# MQTTGateWay.net
KiCad netlist of a schematic drawn in EAGLE
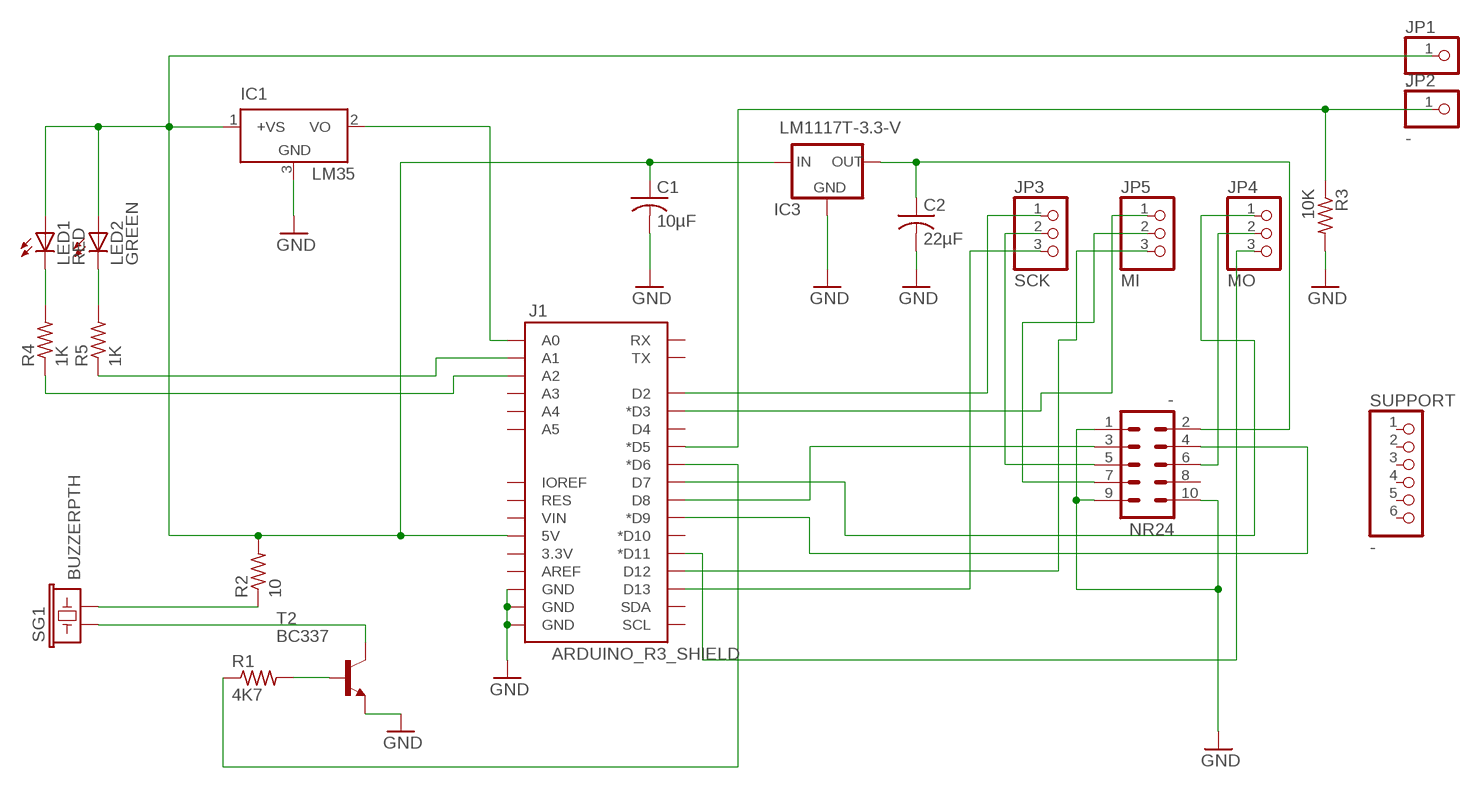
[diagram p0: schematic, sheet 1]

(export (version "E")
  (design (tool "Eeschema 10.0.6"))
  (components
    (comp (ref "C1")
      (value "10µF")
      (footprint "eagle-import:C025-024X044")
      (libsource (lib "eagle-import") (part "C-US025-024X044"))
    )
    (comp (ref "C2")
      (value "22µF")
      (footprint "eagle-import:C025-024X044")
      (libsource (lib "eagle-import") (part "C-US025-024X044"))
    )
    (comp (ref "IC1")
      (value "LM35")
      (footprint "eagle-import:TO92")
      (libsource (lib "eagle-import") (part "LM35CZ"))
    )
    (comp (ref "IC3")
      (value "LM1117T-3.3-V")
      (footprint "eagle-import:TO220V")
      (libsource (lib "eagle-import") (part "LM1117T--V3.3"))
    )
    (comp (ref "J1")
      (value "ARDUINO_R3_SHIELD")
      (footprint "eagle-import:UNO_R3_SHIELD")
      (libsource (lib "eagle-import") (part "ARDUINO_R3_SHIELD"))
    )
    (comp (ref "JP1")
      (value "-")
      (footprint "eagle-import:1X01")
      (libsource (lib "eagle-import") (part "PINHD-1X1"))
    )
    (comp (ref "JP2")
      (value "-")
      (footprint "eagle-import:1X01")
      (libsource (lib "eagle-import") (part "PINHD-1X1"))
    )
    (comp (ref "JP3")
      (value "SCK")
      (footprint "eagle-import:1X03")
      (libsource (lib "eagle-import") (part "PINHD-1X3"))
    )
    (comp (ref "JP4")
      (value "MO")
      (footprint "eagle-import:1X03")
      (libsource (lib "eagle-import") (part "PINHD-1X3"))
    )
    (comp (ref "JP5")
      (value "MI")
      (footprint "eagle-import:1X03")
      (libsource (lib "eagle-import") (part "PINHD-1X3"))
    )
    (comp (ref "LED1")
      (value "RED")
      (footprint "eagle-import:LED3MM")
      (libsource (lib "eagle-import") (part "LED3MM"))
    )
    (comp (ref "LED2")
      (value "GREEN")
      (footprint "eagle-import:LED3MM")
      (libsource (lib "eagle-import") (part "LED3MM"))
    )
    (comp (ref "NR24")
      (value "-")
      (footprint "eagle-import:MA05-2")
      (libsource (lib "eagle-import") (part "MA05-2"))
    )
    (comp (ref "R1")
      (value "4K7")
      (footprint "eagle-import:0207_10")
      (libsource (lib "eagle-import") (part "R-US_0207/10"))
    )
    (comp (ref "R2")
      (value "10")
      (footprint "eagle-import:0207_10")
      (libsource (lib "eagle-import") (part "R-US_0207/10"))
    )
    (comp (ref "R3")
      (value "10K")
      (footprint "eagle-import:0207_10")
      (libsource (lib "eagle-import") (part "R-US_0207/10"))
    )
    (comp (ref "R4")
      (value "1K")
      (footprint "eagle-import:0207_10")
      (libsource (lib "eagle-import") (part "R-US_0207/10"))
    )
    (comp (ref "R5")
      (value "1K")
      (footprint "eagle-import:0207_10")
      (libsource (lib "eagle-import") (part "R-US_0207/10"))
    )
    (comp (ref "SG1")
      (value "BUZZERPTH")
      (footprint "eagle-import:BUZZER-12MM")
      (libsource (lib "eagle-import") (part "BUZZERPTH"))
    )
    (comp (ref "SUPPORT")
      (value "-")
      (footprint "eagle-import:1X06")
      (libsource (lib "eagle-import") (part "PINHD-1X6"))
    )
    (comp (ref "T2")
      (value "BC337")
      (footprint "eagle-import:TO92")
      (libsource (lib "eagle-import") (part "BC337"))
    )
  )
  (nets
    (net (code "1") (name "GND") (class "Default")
      (node (ref "C1") (pin "2") (pinfunction "2_2") (pintype "passive"))
      (node (ref "C2") (pin "2") (pinfunction "2_2") (pintype "passive"))
      (node (ref "IC1") (pin "3") (pinfunction "GND_3") (pintype "power_in"))
      (node (ref "IC3") (pin "1") (pinfunction "GND_1") (pintype "input"))
      (node (ref "J1") (pin "GND@0") (pinfunction "GND_GND@0") (pintype "bidirectional"))
      (node (ref "J1") (pin "GND@1") (pinfunction "GND_GND@1") (pintype "bidirectional"))
      (node (ref "J1") (pin "GND@2") (pinfunction "GND_GND@2") (pintype "bidirectional"))
      (node (ref "NR24") (pin "1") (pinfunction "1_1") (pintype "passive"))
      (node (ref "NR24") (pin "10") (pinfunction "10_10") (pintype "passive"))
      (node (ref "NR24") (pin "9") (pinfunction "9_9") (pintype "passive"))
      (node (ref "R3") (pin "2") (pinfunction "2_2") (pintype "passive"))
      (node (ref "T2") (pin "1") (pinfunction "E_1") (pintype "passive"))
    )
    (net (code "2") (name "Net-(IC1-+VS)") (class "Default")
      (node (ref "C1") (pin "1") (pinfunction "1_1") (pintype "passive"))
      (node (ref "IC1") (pin "1") (pinfunction "+VS_1") (pintype "input"))
      (node (ref "IC3") (pin "3") (pinfunction "IN_3") (pintype "input"))
      (node (ref "J1") (pin "5V") (pinfunction "5V_5V") (pintype "bidirectional"))
      (node (ref "JP1") (pin "1") (pinfunction "1_1") (pintype "passive"))
      (node (ref "LED1") (pin "A") (pinfunction "A_A") (pintype "passive"))
      (node (ref "LED2") (pin "A") (pinfunction "A_A") (pintype "passive"))
      (node (ref "R2") (pin "2") (pinfunction "2_2") (pintype "passive"))
    )
    (net (code "3") (name "Net-(IC1-VO)") (class "Default")
      (node (ref "IC1") (pin "2") (pinfunction "VO_2") (pintype "input"))
      (node (ref "J1") (pin "A0") (pinfunction "A0_A0") (pintype "bidirectional"))
    )
    (net (code "4") (name "Net-(IC3-OUT)") (class "Default")
      (node (ref "C2") (pin "1") (pinfunction "1_1") (pintype "passive"))
      (node (ref "IC3") (pin "2") (pinfunction "OUT_2") (pintype "passive"))
      (node (ref "NR24") (pin "2") (pinfunction "2_2") (pintype "passive"))
    )
    (net (code "5") (name "Net-(J1-*D3)") (class "Default")
      (node (ref "J1") (pin "D3") (pinfunction "*D3_D3") (pintype "bidirectional"))
      (node (ref "JP5") (pin "1") (pinfunction "1_1") (pintype "passive"))
    )
    (net (code "6") (name "Net-(J1-*D5)") (class "Default")
      (node (ref "J1") (pin "D5") (pinfunction "*D5_D5") (pintype "bidirectional"))
      (node (ref "JP2") (pin "1") (pinfunction "1_1") (pintype "passive"))
      (node (ref "R3") (pin "1") (pinfunction "1_1") (pintype "passive"))
    )
    (net (code "7") (name "Net-(J1-*D6)") (class "Default")
      (node (ref "J1") (pin "D6") (pinfunction "*D6_D6") (pintype "bidirectional"))
      (node (ref "R1") (pin "1") (pinfunction "1_1") (pintype "passive"))
    )
    (net (code "8") (name "Net-(J1-*D9)") (class "Default")
      (node (ref "J1") (pin "D9") (pinfunction "*D9_D9") (pintype "bidirectional"))
      (node (ref "NR24") (pin "4") (pinfunction "4_4") (pintype "passive"))
    )
    (net (code "9") (name "Net-(J1-*D11)") (class "Default")
      (node (ref "J1") (pin "D11") (pinfunction "*D11_D11") (pintype "bidirectional"))
      (node (ref "JP4") (pin "3") (pinfunction "3_3") (pintype "passive"))
    )
    (net (code "10") (name "Net-(J1-PadA1)") (class "Default")
      (node (ref "J1") (pin "A1") (pinfunction "A1_A1") (pintype "bidirectional"))
      (node (ref "R5") (pin "1") (pinfunction "1_1") (pintype "passive"))
    )
    (net (code "11") (name "Net-(J1-PadA2)") (class "Default")
      (node (ref "J1") (pin "A2") (pinfunction "A2_A2") (pintype "bidirectional"))
      (node (ref "R4") (pin "1") (pinfunction "1_1") (pintype "passive"))
    )
    (net (code "12") (name "Net-(J1-PadD2)") (class "Default")
      (node (ref "J1") (pin "D2") (pinfunction "D2_D2") (pintype "bidirectional"))
      (node (ref "JP3") (pin "1") (pinfunction "1_1") (pintype "passive"))
    )
    (net (code "13") (name "Net-(J1-PadD7)") (class "Default")
      (node (ref "J1") (pin "D7") (pinfunction "D7_D7") (pintype "bidirectional"))
      (node (ref "JP4") (pin "1") (pinfunction "1_1") (pintype "passive"))
    )
    (net (code "14") (name "Net-(J1-PadD8)") (class "Default")
      (node (ref "J1") (pin "D8") (pinfunction "D8_D8") (pintype "bidirectional"))
      (node (ref "NR24") (pin "3") (pinfunction "3_3") (pintype "passive"))
    )
    (net (code "15") (name "Net-(J1-PadD12)") (class "Default")
      (node (ref "J1") (pin "D12") (pinfunction "D12_D12") (pintype "bidirectional"))
      (node (ref "JP5") (pin "3") (pinfunction "3_3") (pintype "passive"))
    )
    (net (code "16") (name "Net-(J1-PadD13)") (class "Default")
      (node (ref "J1") (pin "D13") (pinfunction "D13_D13") (pintype "bidirectional"))
      (node (ref "JP3") (pin "3") (pinfunction "3_3") (pintype "passive"))
    )
    (net (code "17") (name "Net-(JP3-Pad2)") (class "Default")
      (node (ref "JP3") (pin "2") (pinfunction "2_2") (pintype "passive"))
      (node (ref "NR24") (pin "5") (pinfunction "5_5") (pintype "passive"))
    )
    (net (code "18") (name "Net-(JP4-Pad2)") (class "Default")
      (node (ref "JP4") (pin "2") (pinfunction "2_2") (pintype "passive"))
      (node (ref "NR24") (pin "6") (pinfunction "6_6") (pintype "passive"))
    )
    (net (code "19") (name "Net-(JP5-Pad2)") (class "Default")
      (node (ref "JP5") (pin "2") (pinfunction "2_2") (pintype "passive"))
      (node (ref "NR24") (pin "7") (pinfunction "7_7") (pintype "passive"))
    )
    (net (code "20") (name "Net-(LED1-C)") (class "Default")
      (node (ref "LED1") (pin "K") (pinfunction "C_K") (pintype "passive"))
      (node (ref "R4") (pin "2") (pinfunction "2_2") (pintype "passive"))
    )
    (net (code "21") (name "Net-(LED2-C)") (class "Default")
      (node (ref "LED2") (pin "K") (pinfunction "C_K") (pintype "passive"))
      (node (ref "R5") (pin "2") (pinfunction "2_2") (pintype "passive"))
    )
    (net (code "22") (name "Net-(SG1-1)") (class "Default")
      (node (ref "SG1") (pin "+") (pinfunction "1_+") (pintype "passive"))
      (node (ref "T2") (pin "3") (pinfunction "C_3") (pintype "passive"))
    )
    (net (code "23") (name "Net-(SG1-2)") (class "Default")
      (node (ref "R2") (pin "1") (pinfunction "1_1") (pintype "passive"))
      (node (ref "SG1") (pin "-") (pinfunction "2_-") (pintype "passive"))
    )
    (net (code "24") (name "Net-(T2-B)") (class "Default")
      (node (ref "R1") (pin "2") (pinfunction "2_2") (pintype "passive"))
      (node (ref "T2") (pin "2") (pinfunction "B_2") (pintype "passive"))
    )
    (net (code "25") (name "unconnected-(J1-*D10-PadD10)") (class "Default")
      (node (ref "J1") (pin "D10") (pinfunction "*D10_D10") (pintype "bidirectional"))
    )
    (net (code "26") (name "unconnected-(J1-Pad3.3V)") (class "Default")
      (node (ref "J1") (pin "3.3V") (pinfunction "3.3V_3.3V") (pintype "bidirectional"))
    )
    (net (code "27") (name "unconnected-(J1-PadA3)") (class "Default")
      (node (ref "J1") (pin "A3") (pinfunction "A3_A3") (pintype "bidirectional"))
    )
    (net (code "28") (name "unconnected-(J1-PadA4)") (class "Default")
      (node (ref "J1") (pin "A4") (pinfunction "A4_A4") (pintype "bidirectional"))
    )
    (net (code "29") (name "unconnected-(J1-PadA5)") (class "Default")
      (node (ref "J1") (pin "A5") (pinfunction "A5_A5") (pintype "bidirectional"))
    )
    (net (code "30") (name "unconnected-(J1-PadAREF)") (class "Default")
      (node (ref "J1") (pin "AREF") (pinfunction "AREF_AREF") (pintype "bidirectional"))
    )
    (net (code "31") (name "unconnected-(J1-PadD4)") (class "Default")
      (node (ref "J1") (pin "D4") (pinfunction "D4_D4") (pintype "bidirectional"))
    )
    (net (code "32") (name "unconnected-(J1-PadIOREF)") (class "Default")
      (node (ref "J1") (pin "IOREF") (pinfunction "IOREF_IOREF") (pintype "bidirectional"))
    )
    (net (code "33") (name "unconnected-(J1-PadRES)") (class "Default")
      (node (ref "J1") (pin "RES") (pinfunction "RES_RES") (pintype "bidirectional"))
    )
    (net (code "34") (name "unconnected-(J1-PadRX)") (class "Default")
      (node (ref "J1") (pin "RX") (pinfunction "RX_RX") (pintype "bidirectional"))
    )
    (net (code "35") (name "unconnected-(J1-PadSCL)") (class "Default")
      (node (ref "J1") (pin "SCL") (pinfunction "SCL_SCL") (pintype "bidirectional"))
    )
    (net (code "36") (name "unconnected-(J1-PadSDA)") (class "Default")
      (node (ref "J1") (pin "SDA") (pinfunction "SDA_SDA") (pintype "bidirectional"))
    )
    (net (code "37") (name "unconnected-(J1-PadTX)") (class "Default")
      (node (ref "J1") (pin "TX") (pinfunction "TX_TX") (pintype "bidirectional"))
    )
    (net (code "38") (name "unconnected-(J1-PadVIN)") (class "Default")
      (node (ref "J1") (pin "VIN") (pinfunction "VIN_VIN") (pintype "bidirectional"))
    )
    (net (code "39") (name "unconnected-(NR24-Pad8)") (class "Default")
      (node (ref "NR24") (pin "8") (pinfunction "8_8") (pintype "passive"))
    )
    (net (code "40") (name "unconnected-(SUPPORT-Pad1)") (class "Default")
      (node (ref "SUPPORT") (pin "1") (pinfunction "1_1") (pintype "passive"))
    )
    (net (code "41") (name "unconnected-(SUPPORT-Pad2)") (class "Default")
      (node (ref "SUPPORT") (pin "2") (pinfunction "2_2") (pintype "passive"))
    )
    (net (code "42") (name "unconnected-(SUPPORT-Pad3)") (class "Default")
      (node (ref "SUPPORT") (pin "3") (pinfunction "3_3") (pintype "passive"))
    )
    (net (code "43") (name "unconnected-(SUPPORT-Pad4)") (class "Default")
      (node (ref "SUPPORT") (pin "4") (pinfunction "4_4") (pintype "passive"))
    )
    (net (code "44") (name "unconnected-(SUPPORT-Pad5)") (class "Default")
      (node (ref "SUPPORT") (pin "5") (pinfunction "5_5") (pintype "passive"))
    )
    (net (code "45") (name "unconnected-(SUPPORT-Pad6)") (class "Default")
      (node (ref "SUPPORT") (pin "6") (pinfunction "6_6") (pintype "passive"))
    )
  )
)
